# eagle_eagle_Tiltaudio_3_6.net
KiCad netlist of a schematic drawn in EAGLE
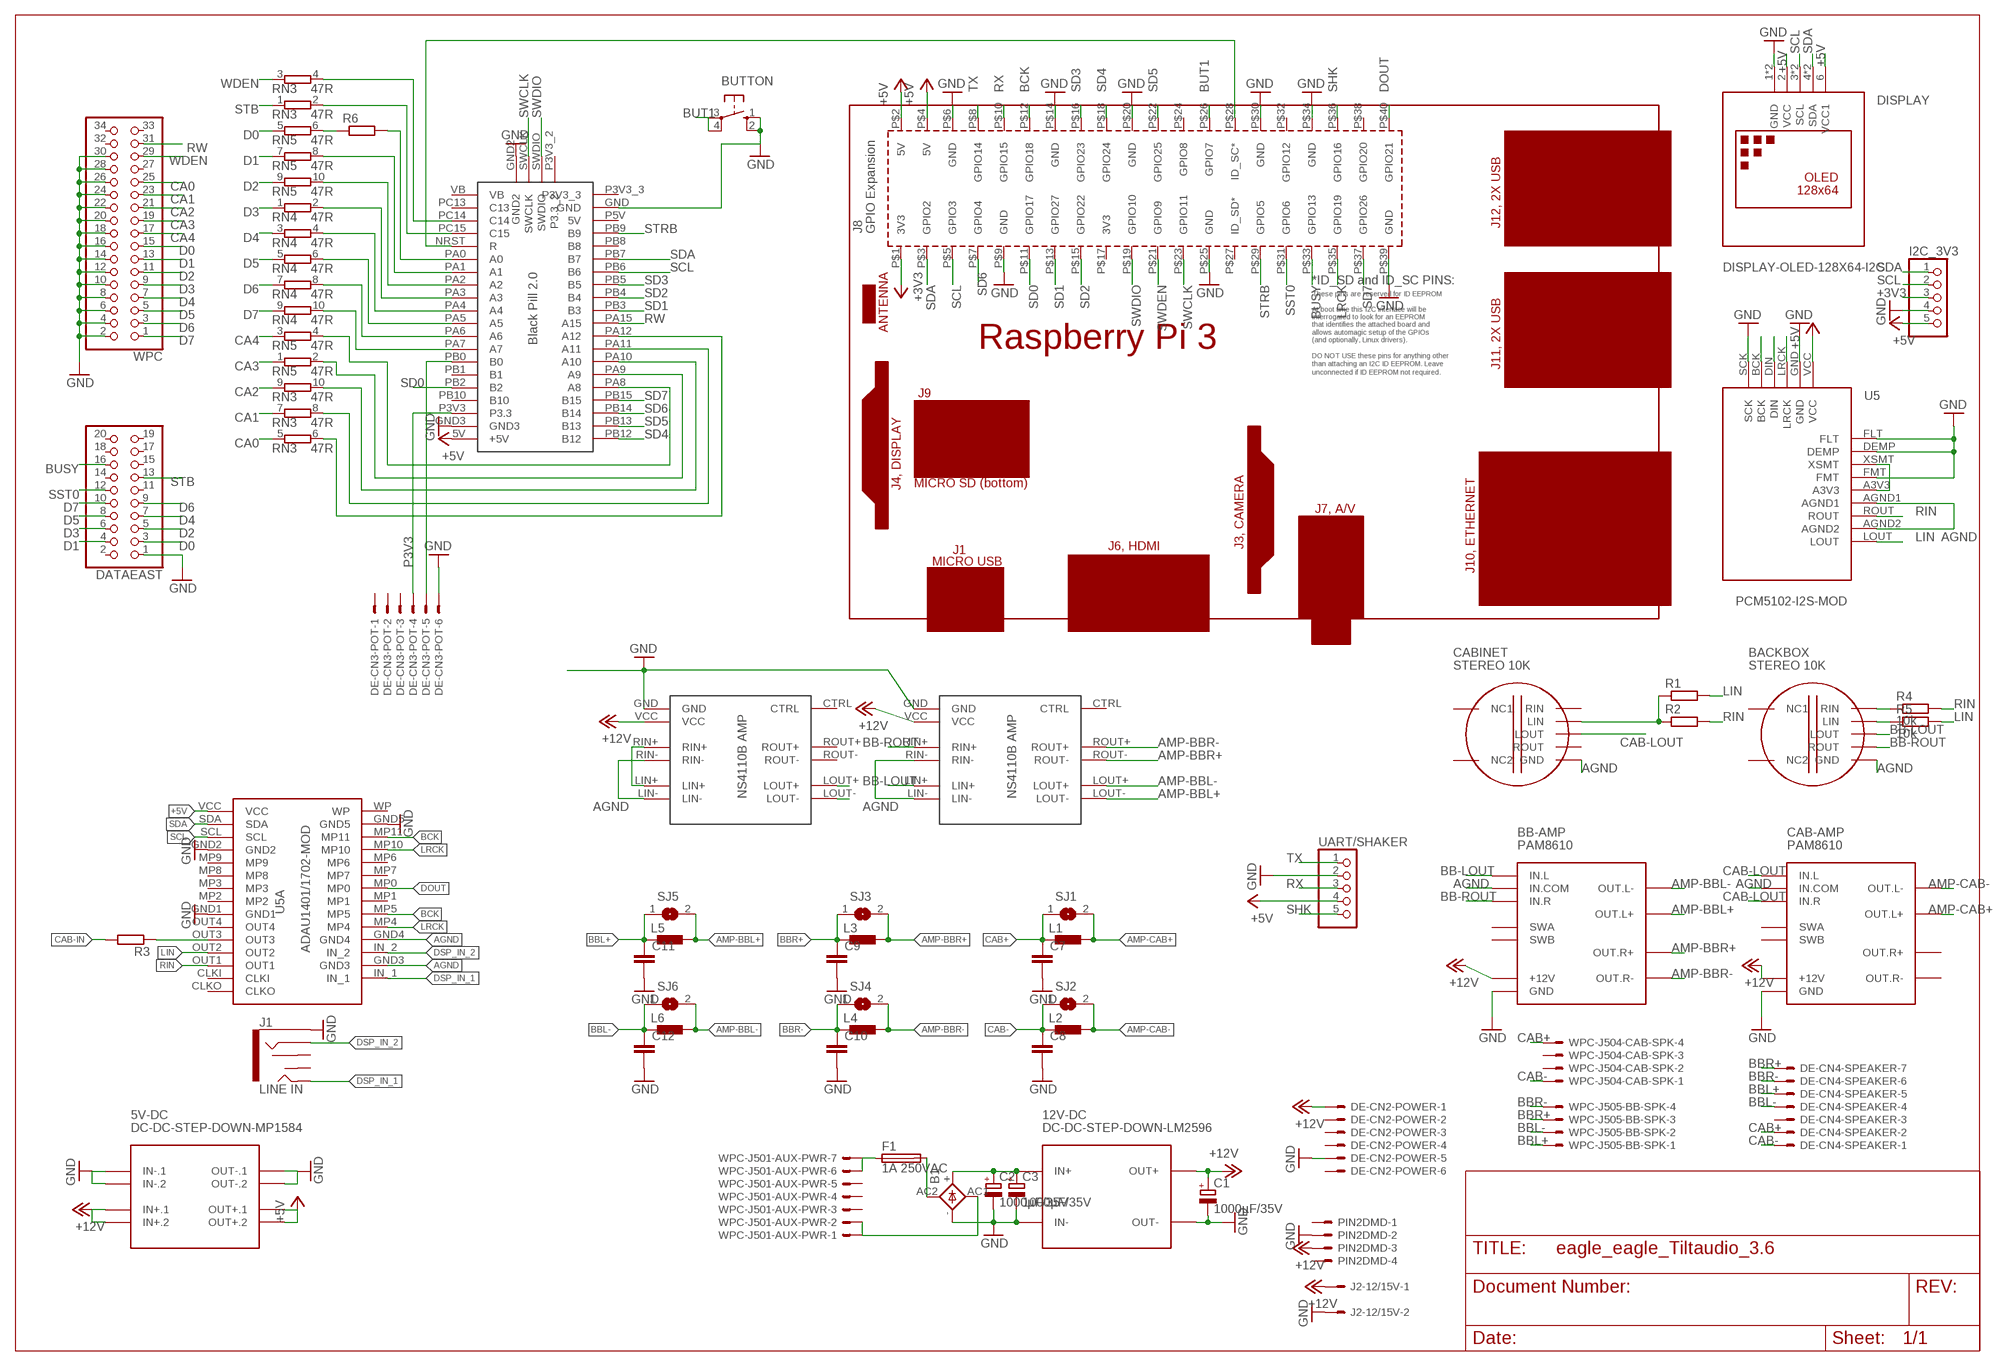
[diagram p0: schematic, sheet 1]

(export (version "E")
  (design (tool "Eeschema 10.0.6"))
  (components
    (comp (ref "5V-DC")
      (value "DC-DC-STEP-DOWN-MP1584")
      (footprint "eagle-import:DC-DC-STEP-DOWN-MP1584")
      (libsource (lib "eagle-import") (part "DC-DC-STEP-DOWN-MP1584"))
    )
    (comp (ref "12V-DC")
      (value "DC-DC-STEP-DOWN-LM2596")
      (footprint "eagle-import:DC-DC-STEP-DOWN-LM2596")
      (libsource (lib "eagle-import") (part "DC-DC-STEP-DOWN-LM2596"))
    )
    (comp (ref "B1")
      (value "KBL")
      (footprint "eagle-import:KBL")
      (libsource (lib "eagle-import") (part "KBL"))
    )
    (comp (ref "BACKBOX")
      (value "STEREO 10K")
      (footprint "eagle-import:UXCELL-STEREO-POTENTIOMETER")
      (libsource (lib "eagle-import") (part "UXCELL-STEREO-POTENTIOMETER"))
    )
    (comp (ref "BB-AMP")
      (value "PAM8610")
      (footprint "eagle-import:AMPLIFIER-PAM8610")
      (libsource (lib "eagle-import") (part "AMPLIFIER-PAM8610"))
    )
    (comp (ref "BUTTON")
      (value "10-XX")
      (footprint "eagle-import:B3F-10XX")
      (fields (field (name "MPN") "B3F-1000"))
      (libsource (lib "eagle-import") (part "10-XX"))
    )
    (comp (ref "C1")
      (value "1000µF/35V")
      (footprint "eagle-import:E5-13")
      (libsource (lib "eagle-import") (part "CPOL-EUE5-13"))
    )
    (comp (ref "C2")
      (value "1000µF/35V")
      (footprint "eagle-import:E5-13")
      (libsource (lib "eagle-import") (part "CPOL-EUE5-13"))
    )
    (comp (ref "C3")
      (value "1000µF/35V")
      (footprint "eagle-import:E5-13")
      (libsource (lib "eagle-import") (part "CPOL-EUE5-13"))
    )
    (comp (ref "C7")
      (value "C-EU050-025X075")
      (footprint "eagle-import:C050-025X075")
      (libsource (lib "eagle-import") (part "C-EU050-025X075"))
    )
    (comp (ref "C8")
      (value "C-EU050-025X075")
      (footprint "eagle-import:C050-025X075")
      (libsource (lib "eagle-import") (part "C-EU050-025X075"))
    )
    (comp (ref "C9")
      (value "C-EU050-025X075")
      (footprint "eagle-import:C050-025X075")
      (libsource (lib "eagle-import") (part "C-EU050-025X075"))
    )
    (comp (ref "C10")
      (value "C-EU050-025X075")
      (footprint "eagle-import:C050-025X075")
      (libsource (lib "eagle-import") (part "C-EU050-025X075"))
    )
    (comp (ref "C11")
      (value "C-EU050-025X075")
      (footprint "eagle-import:C050-025X075")
      (libsource (lib "eagle-import") (part "C-EU050-025X075"))
    )
    (comp (ref "C12")
      (value "C-EU050-025X075")
      (footprint "eagle-import:C050-025X075")
      (libsource (lib "eagle-import") (part "C-EU050-025X075"))
    )
    (comp (ref "CAB-AMP")
      (value "PAM8610")
      (footprint "eagle-import:AMPLIFIER-PAM8610")
      (libsource (lib "eagle-import") (part "AMPLIFIER-PAM8610"))
    )
    (comp (ref "CABINET")
      (value "STEREO 10K")
      (footprint "eagle-import:UXCELL-STEREO-POTENTIOMETER")
      (libsource (lib "eagle-import") (part "UXCELL-STEREO-POTENTIOMETER"))
    )
    (comp (ref "DATAEAST")
      (value "PINHD-2X10")
      (footprint "eagle-import:2X10")
      (libsource (lib "eagle-import") (part "PINHD-2X10"))
    )
    (comp (ref "DE-CN2-POWER")
      (value "KK-156-6")
      (footprint "eagle-import:KK-156-6")
      (libsource (lib "eagle-import") (part "KK-156-6"))
    )
    (comp (ref "DE-CN3-POT")
      (value "KK-156-6")
      (footprint "eagle-import:KK-156-6")
      (libsource (lib "eagle-import") (part "KK-156-6"))
    )
    (comp (ref "DE-CN4-SPEAKER")
      (value "KK-156-7")
      (footprint "eagle-import:KK-156-7")
      (libsource (lib "eagle-import") (part "KK-156-7"))
    )
    (comp (ref "DISPLAY")
      (value "DISPLAY-OLED-128X64-I2C")
      (footprint "eagle-import:DISPLAY-OLED-128X64-I2C")
      (libsource (lib "eagle-import") (part "DISPLAY-OLED-128X64-I2C"))
    )
    (comp (ref "F1")
      (value "1A 250VAC")
      (footprint "eagle-import:SHK20L")
      (libsource (lib "eagle-import") (part "FUSESHK20L"))
    )
    (comp (ref "I2C_3V3")
      (value "PINHD-1X5")
      (footprint "eagle-import:1X05")
      (libsource (lib "eagle-import") (part "PINHD-1X5"))
    )
    (comp (ref "J1")
      (value "LINE IN")
      (footprint "eagle-import:AUDIO-JACK")
      (libsource (lib "eagle-import") (part "AUDIO_JACK_3.5MM_PTH"))
    )
    (comp (ref "J2-12/15V")
      (value "KK-156-2")
      (footprint "eagle-import:KK-156-2")
      (libsource (lib "eagle-import") (part "KK-156-2"))
    )
    (comp (ref "L1")
      (value "BL02RN1")
      (footprint "eagle-import:BL02RN1")
      (libsource (lib "eagle-import") (part "BL02RN1"))
    )
    (comp (ref "L2")
      (value "BL02RN1")
      (footprint "eagle-import:BL02RN1")
      (libsource (lib "eagle-import") (part "BL02RN1"))
    )
    (comp (ref "L3")
      (value "BL02RN1")
      (footprint "eagle-import:BL02RN1")
      (libsource (lib "eagle-import") (part "BL02RN1"))
    )
    (comp (ref "L4")
      (value "BL02RN1")
      (footprint "eagle-import:BL02RN1")
      (libsource (lib "eagle-import") (part "BL02RN1"))
    )
    (comp (ref "L5")
      (value "BL02RN1")
      (footprint "eagle-import:BL02RN1")
      (libsource (lib "eagle-import") (part "BL02RN1"))
    )
    (comp (ref "L6")
      (value "BL02RN1")
      (footprint "eagle-import:BL02RN1")
      (libsource (lib "eagle-import") (part "BL02RN1"))
    )
    (comp (ref "MPU1")
      (value "Raspberry Pi3")
      (footprint "eagle-import:RPI3MIRROR")
      (libsource (lib "eagle-import") (part "RPI3RPI3MIRROR"))
    )
    (comp (ref "PIN2DMD")
      (value "KK-156-4")
      (footprint "eagle-import:KK-156-4")
      (libsource (lib "eagle-import") (part "KK-156-4"))
    )
    (comp (ref "R1")
      (value "R-EU_0207/10")
      (footprint "eagle-import:0207_10")
      (libsource (lib "eagle-import") (part "R-EU_0207/10"))
    )
    (comp (ref "R2")
      (value "R-EU_0207/10")
      (footprint "eagle-import:0207_10")
      (libsource (lib "eagle-import") (part "R-EU_0207/10"))
    )
    (comp (ref "R3")
      (value "R-EU_0207/10")
      (footprint "eagle-import:0207_10")
      (libsource (lib "eagle-import") (part "R-EU_0207/10"))
    )
    (comp (ref "R4")
      (value "10k")
      (footprint "eagle-import:0207_10")
      (libsource (lib "eagle-import") (part "R-EU_0207/10"))
    )
    (comp (ref "R5")
      (value "10k")
      (footprint "eagle-import:0207_10")
      (libsource (lib "eagle-import") (part "R-EU_0207/10"))
    )
    (comp (ref "R6")
      (value "R-EU_0207/12")
      (footprint "eagle-import:0207_12")
      (libsource (lib "eagle-import") (part "R-EU_0207/12"))
    )
    (comp (ref "RN3")
      (value "47R")
      (footprint "eagle-import:SIL10")
      (libsource (lib "eagle-import") (part "E5RP"))
    )
    (comp (ref "RN4")
      (value "47R")
      (footprint "eagle-import:SIL10")
      (libsource (lib "eagle-import") (part "E5RP"))
    )
    (comp (ref "RN5")
      (value "47R")
      (footprint "eagle-import:SIL10")
      (libsource (lib "eagle-import") (part "E5RP"))
    )
    (comp (ref "SJ1") (value "SJ") (footprint "eagle-import:SJ") (libsource (lib "eagle-import") (part "SJ")))
    (comp (ref "SJ2") (value "SJ") (footprint "eagle-import:SJ") (libsource (lib "eagle-import") (part "SJ")))
    (comp (ref "SJ3") (value "SJ") (footprint "eagle-import:SJ") (libsource (lib "eagle-import") (part "SJ")))
    (comp (ref "SJ4") (value "SJ") (footprint "eagle-import:SJ") (libsource (lib "eagle-import") (part "SJ")))
    (comp (ref "SJ5") (value "SJ") (footprint "eagle-import:SJ") (libsource (lib "eagle-import") (part "SJ")))
    (comp (ref "SJ6") (value "SJ") (footprint "eagle-import:SJ") (libsource (lib "eagle-import") (part "SJ")))
    (comp (ref "U$1")
      (value "STM32F411CE-BLACKPILL")
      (footprint "eagle-import:DIL40")
      (libsource (lib "eagle-import") (part "STM32F411CE-BLACKPILL"))
    )
    (comp (ref "U$2")
      (value "DAMP")
      (footprint "eagle-import:DAMP")
      (libsource (lib "eagle-import") (part "DAMP"))
    )
    (comp (ref "U$3")
      (value "DAMP")
      (footprint "eagle-import:DAMP")
      (libsource (lib "eagle-import") (part "DAMP"))
    )
    (comp (ref "U5")
      (value "PCM5102-I2S-MOD")
      (footprint "eagle-import:PCM5102-I2S-MOD")
      (libsource (lib "eagle-import") (part "PCM5102-I2S-MOD"))
    )
    (comp (ref "U5A")
      (value "ADAU1401/1702-MOD")
      (footprint "eagle-import:ADAU1401_1701-MOD")
      (libsource (lib "eagle-import") (part "ADAU1401/1702-MOD"))
    )
    (comp (ref "UART/SHAKER")
      (value "PINHD-1X5")
      (footprint "eagle-import:1X05")
      (libsource (lib "eagle-import") (part "PINHD-1X5"))
    )
    (comp (ref "WPC")
      (value "PINHD-2X17")
      (footprint "eagle-import:2X17")
      (libsource (lib "eagle-import") (part "PINHD-2X17"))
    )
    (comp (ref "WPC-J501-AUX-PWR")
      (value "KK-156-7")
      (footprint "eagle-import:KK-156-7")
      (libsource (lib "eagle-import") (part "KK-156-7"))
    )
    (comp (ref "WPC-J504-CAB-SPK")
      (value "KK-156-4")
      (footprint "eagle-import:KK-156-4")
      (libsource (lib "eagle-import") (part "KK-156-4"))
    )
    (comp (ref "WPC-J505-BB-SPK")
      (value "KK-156-4")
      (footprint "eagle-import:KK-156-4")
      (libsource (lib "eagle-import") (part "KK-156-4"))
    )
  )
  (nets
    (net (code "1") (name "+3V3") (class "Default")
      (node (ref "I2C_3V3") (pin "3") (pinfunction "3_3") (pintype "passive"))
      (node (ref "MPU1") (pin "P$1") (pinfunction "3V3_P$1") (pintype "bidirectional"))
    )
    (net (code "2") (name "+5V") (class "Default")
      (node (ref "5V-DC") (pin "OUT+.1") (pinfunction "OUT+.1_OUT+.1") (pintype "bidirectional"))
      (node (ref "5V-DC") (pin "OUT+.2") (pinfunction "OUT+.2_OUT+.2") (pintype "bidirectional"))
      (node (ref "DISPLAY") (pin "2") (pinfunction "VCC_2") (pintype "power_in"))
      (node (ref "DISPLAY") (pin "6") (pinfunction "VCC1_6") (pintype "power_in"))
      (node (ref "I2C_3V3") (pin "5") (pinfunction "5_5") (pintype "passive"))
      (node (ref "MPU1") (pin "P$2") (pinfunction "5V_P$2") (pintype "bidirectional"))
      (node (ref "MPU1") (pin "P$4") (pinfunction "5V_P$4") (pintype "bidirectional"))
      (node (ref "U$1") (pin "5V") (pinfunction "+5V_5V") (pintype "bidirectional"))
      (node (ref "U5") (pin "VCC") (pinfunction "VCC_VCC") (pintype "bidirectional"))
      (node (ref "U5A") (pin "VCC") (pinfunction "VCC_VCC") (pintype "bidirectional"))
      (node (ref "UART/SHAKER") (pin "4") (pinfunction "4_4") (pintype "passive"))
    )
    (net (code "3") (name "+12V") (class "Default")
      (node (ref "12V-DC") (pin "OUT+") (pinfunction "OUT+_OUT+") (pintype "bidirectional"))
      (node (ref "5V-DC") (pin "IN+.1") (pinfunction "IN+.1_IN+.1") (pintype "bidirectional"))
      (node (ref "5V-DC") (pin "IN+.2") (pinfunction "IN+.2_IN+.2") (pintype "bidirectional"))
      (node (ref "BB-AMP") (pin "+12V") (pinfunction "+12V_+12V") (pintype "power_in"))
      (node (ref "C1") (pin "+") (pinfunction "+_+") (pintype "passive"))
      (node (ref "CAB-AMP") (pin "+12V") (pinfunction "+12V_+12V") (pintype "power_in"))
      (node (ref "DE-CN2-POWER") (pin "1") (pinfunction "S_1") (pintype "passive"))
      (node (ref "J2-12/15V") (pin "1") (pinfunction "S_1") (pintype "passive"))
      (node (ref "PIN2DMD") (pin "3") (pinfunction "S_3") (pintype "passive"))
      (node (ref "U$2") (pin "VCC") (pinfunction "VCC_VCC") (pintype "bidirectional"))
      (node (ref "U$3") (pin "VCC") (pinfunction "VCC_VCC") (pintype "bidirectional"))
    )
    (net (code "4") (name "/BB-LOUT") (class "Default")
      (node (ref "BACKBOX") (pin "LOUT") (pinfunction "LOUT_LOUT") (pintype "bidirectional"))
      (node (ref "BB-AMP") (pin "IN.L") (pinfunction "IN.L_IN.L") (pintype "input"))
      (node (ref "U$2") (pin "LIN+") (pinfunction "LIN+_LIN+") (pintype "bidirectional"))
    )
    (net (code "5") (name "/BB-ROUT") (class "Default")
      (node (ref "BACKBOX") (pin "ROUT") (pinfunction "ROUT_ROUT") (pintype "bidirectional"))
      (node (ref "BB-AMP") (pin "IN.R") (pinfunction "IN.R_IN.R") (pintype "bidirectional"))
      (node (ref "U$2") (pin "RIN+") (pinfunction "RIN+_RIN+") (pintype "bidirectional"))
    )
    (net (code "6") (name "/BUSY") (class "Default")
      (node (ref "DATAEAST") (pin "16") (pinfunction "16_16") (pintype "passive"))
      (node (ref "MPU1") (pin "P$33") (pinfunction "GPIO13_P$33") (pintype "bidirectional"))
    )
    (net (code "7") (name "/BUT1") (class "Default")
      (node (ref "BUTTON") (pin "3") (pinfunction "P_3") (pintype "passive"))
      (node (ref "BUTTON") (pin "4") (pinfunction "P1_4") (pintype "passive"))
      (node (ref "MPU1") (pin "P$26") (pinfunction "GPIO7_P$26") (pintype "bidirectional"))
    )
    (net (code "8") (name "/CA0") (class "Default")
      (node (ref "RN3") (pin "5") (pinfunction "1_5") (pintype "passive"))
      (node (ref "WPC") (pin "25") (pinfunction "25_25") (pintype "passive"))
    )
    (net (code "9") (name "/CA1") (class "Default")
      (node (ref "RN3") (pin "7") (pinfunction "1_7") (pintype "passive"))
      (node (ref "WPC") (pin "23") (pinfunction "23_23") (pintype "passive"))
    )
    (net (code "10") (name "/CA2") (class "Default")
      (node (ref "RN3") (pin "9") (pinfunction "1_9") (pintype "passive"))
      (node (ref "WPC") (pin "21") (pinfunction "21_21") (pintype "passive"))
    )
    (net (code "11") (name "/CA3") (class "Default")
      (node (ref "RN5") (pin "1") (pinfunction "1_1") (pintype "passive"))
      (node (ref "WPC") (pin "19") (pinfunction "19_19") (pintype "passive"))
    )
    (net (code "12") (name "/CA4") (class "Default")
      (node (ref "RN5") (pin "3") (pinfunction "1_3") (pintype "passive"))
      (node (ref "WPC") (pin "17") (pinfunction "17_17") (pintype "passive"))
    )
    (net (code "13") (name "/CAB-LOUT") (class "Default")
      (node (ref "CAB-AMP") (pin "IN.L") (pinfunction "IN.L_IN.L") (pintype "input"))
      (node (ref "CAB-AMP") (pin "IN.R") (pinfunction "IN.R_IN.R") (pintype "bidirectional"))
      (node (ref "CABINET") (pin "LOUT") (pinfunction "LOUT_LOUT") (pintype "bidirectional"))
      (node (ref "U$3") (pin "LIN+") (pinfunction "LIN+_LIN+") (pintype "bidirectional"))
      (node (ref "U$3") (pin "RIN+") (pinfunction "RIN+_RIN+") (pintype "bidirectional"))
    )
    (net (code "14") (name "/D0") (class "Default")
      (node (ref "DATAEAST") (pin "3") (pinfunction "3_3") (pintype "passive"))
      (node (ref "RN5") (pin "5") (pinfunction "1_5") (pintype "passive"))
      (node (ref "WPC") (pin "15") (pinfunction "15_15") (pintype "passive"))
    )
    (net (code "15") (name "/D1") (class "Default")
      (node (ref "DATAEAST") (pin "4") (pinfunction "4_4") (pintype "passive"))
      (node (ref "RN5") (pin "7") (pinfunction "1_7") (pintype "passive"))
      (node (ref "WPC") (pin "13") (pinfunction "13_13") (pintype "passive"))
    )
    (net (code "16") (name "/D2") (class "Default")
      (node (ref "DATAEAST") (pin "5") (pinfunction "5_5") (pintype "passive"))
      (node (ref "RN5") (pin "9") (pinfunction "1_9") (pintype "passive"))
      (node (ref "WPC") (pin "11") (pinfunction "11_11") (pintype "passive"))
    )
    (net (code "17") (name "/D3") (class "Default")
      (node (ref "DATAEAST") (pin "6") (pinfunction "6_6") (pintype "passive"))
      (node (ref "RN4") (pin "1") (pinfunction "1_1") (pintype "passive"))
      (node (ref "WPC") (pin "9") (pinfunction "9_9") (pintype "passive"))
    )
    (net (code "18") (name "/D4") (class "Default")
      (node (ref "DATAEAST") (pin "7") (pinfunction "7_7") (pintype "passive"))
      (node (ref "RN4") (pin "3") (pinfunction "1_3") (pintype "passive"))
      (node (ref "WPC") (pin "7") (pinfunction "7_7") (pintype "passive"))
    )
    (net (code "19") (name "/D5") (class "Default")
      (node (ref "DATAEAST") (pin "8") (pinfunction "8_8") (pintype "passive"))
      (node (ref "RN4") (pin "5") (pinfunction "1_5") (pintype "passive"))
      (node (ref "WPC") (pin "5") (pinfunction "5_5") (pintype "passive"))
    )
    (net (code "20") (name "/D6") (class "Default")
      (node (ref "DATAEAST") (pin "9") (pinfunction "9_9") (pintype "passive"))
      (node (ref "RN4") (pin "7") (pinfunction "1_7") (pintype "passive"))
      (node (ref "WPC") (pin "3") (pinfunction "3_3") (pintype "passive"))
    )
    (net (code "21") (name "/D7") (class "Default")
      (node (ref "DATAEAST") (pin "10") (pinfunction "10_10") (pintype "passive"))
      (node (ref "RN4") (pin "9") (pinfunction "1_9") (pintype "passive"))
      (node (ref "WPC") (pin "1") (pinfunction "1_1") (pintype "passive"))
    )
    (net (code "22") (name "/P3V3") (class "Default")
      (node (ref "DE-CN3-POT") (pin "4") (pinfunction "S_4") (pintype "passive"))
      (node (ref "U$1") (pin "P3V3") (pinfunction "P3.3_P3V3") (pintype "bidirectional"))
    )
    (net (code "23") (name "/RW") (class "Default")
      (node (ref "U$1") (pin "PA15") (pinfunction "A15_PA15") (pintype "bidirectional"))
      (node (ref "WPC") (pin "31") (pinfunction "31_31") (pintype "passive"))
    )
    (net (code "24") (name "/RX") (class "Default")
      (node (ref "MPU1") (pin "P$10") (pinfunction "GPIO15_P$10") (pintype "bidirectional"))
      (node (ref "UART/SHAKER") (pin "3") (pinfunction "3_3") (pintype "passive"))
    )
    (net (code "25") (name "/SD0") (class "Default")
      (node (ref "MPU1") (pin "P$11") (pinfunction "GPIO17_P$11") (pintype "bidirectional"))
      (node (ref "U$1") (pin "PB2") (pinfunction "B2_PB2") (pintype "bidirectional"))
    )
    (net (code "26") (name "/SD1") (class "Default")
      (node (ref "MPU1") (pin "P$13") (pinfunction "GPIO27_P$13") (pintype "bidirectional"))
      (node (ref "U$1") (pin "PB3") (pinfunction "B3_PB3") (pintype "bidirectional"))
    )
    (net (code "27") (name "/SD2") (class "Default")
      (node (ref "MPU1") (pin "P$15") (pinfunction "GPIO22_P$15") (pintype "bidirectional"))
      (node (ref "U$1") (pin "PB4") (pinfunction "B4_PB4") (pintype "bidirectional"))
    )
    (net (code "28") (name "/SD3") (class "Default")
      (node (ref "MPU1") (pin "P$16") (pinfunction "GPIO23_P$16") (pintype "bidirectional"))
      (node (ref "U$1") (pin "PB5") (pinfunction "B5_PB5") (pintype "bidirectional"))
    )
    (net (code "29") (name "/SD4") (class "Default")
      (node (ref "MPU1") (pin "P$18") (pinfunction "GPIO24_P$18") (pintype "bidirectional"))
      (node (ref "U$1") (pin "PB12") (pinfunction "B12_PB12") (pintype "bidirectional"))
    )
    (net (code "30") (name "/SD5") (class "Default")
      (node (ref "MPU1") (pin "P$22") (pinfunction "GPIO25_P$22") (pintype "bidirectional"))
      (node (ref "U$1") (pin "PB13") (pinfunction "B13_PB13") (pintype "bidirectional"))
    )
    (net (code "31") (name "/SD6") (class "Default")
      (node (ref "MPU1") (pin "P$7") (pinfunction "GPIO4_P$7") (pintype "bidirectional"))
      (node (ref "U$1") (pin "PB14") (pinfunction "B14_PB14") (pintype "bidirectional"))
    )
    (net (code "32") (name "/SD7") (class "Default")
      (node (ref "MPU1") (pin "P$37") (pinfunction "GPIO26_P$37") (pintype "bidirectional"))
      (node (ref "U$1") (pin "PB15") (pinfunction "B15_PB15") (pintype "bidirectional"))
    )
    (net (code "33") (name "/SHK") (class "Default")
      (node (ref "MPU1") (pin "P$36") (pinfunction "GPIO16_P$36") (pintype "bidirectional"))
      (node (ref "UART/SHAKER") (pin "5") (pinfunction "5_5") (pintype "passive"))
    )
    (net (code "34") (name "/SST0") (class "Default")
      (node (ref "DATAEAST") (pin "12") (pinfunction "12_12") (pintype "passive"))
      (node (ref "MPU1") (pin "P$31") (pinfunction "GPIO6_P$31") (pintype "bidirectional"))
    )
    (net (code "35") (name "/STB") (class "Default")
      (node (ref "DATAEAST") (pin "13") (pinfunction "13_13") (pintype "passive"))
      (node (ref "RN3") (pin "1") (pinfunction "1_1") (pintype "passive"))
    )
    (net (code "36") (name "/STRB") (class "Default")
      (node (ref "MPU1") (pin "P$29") (pinfunction "GPIO5_P$29") (pintype "bidirectional"))
      (node (ref "U$1") (pin "PB9") (pinfunction "B9_PB9") (pintype "bidirectional"))
    )
    (net (code "37") (name "/SWCLK") (class "Default")
      (node (ref "MPU1") (pin "P$23") (pinfunction "GPIO11_P$23") (pintype "bidirectional"))
      (node (ref "U$1") (pin "SWCLK") (pinfunction "SWCLK_SWCLK") (pintype "bidirectional"))
    )
    (net (code "38") (name "/SWDEN") (class "Default")
      (node (ref "MPU1") (pin "P$21") (pinfunction "GPIO9_P$21") (pintype "bidirectional"))
    )
    (net (code "39") (name "/SWDIO") (class "Default")
      (node (ref "MPU1") (pin "P$19") (pinfunction "GPIO10_P$19") (pintype "bidirectional"))
      (node (ref "U$1") (pin "SWDIO") (pinfunction "SWDIO_SWDIO") (pintype "bidirectional"))
    )
    (net (code "40") (name "/TX") (class "Default")
      (node (ref "MPU1") (pin "P$8") (pinfunction "GPIO14_P$8") (pintype "bidirectional"))
      (node (ref "UART/SHAKER") (pin "1") (pinfunction "1_1") (pintype "passive"))
    )
    (net (code "41") (name "/WDEN") (class "Default")
      (node (ref "RN3") (pin "3") (pinfunction "1_3") (pintype "passive"))
      (node (ref "WPC") (pin "29") (pinfunction "29_29") (pintype "passive"))
    )
    (net (code "42") (name "AGND") (class "Default")
      (node (ref "BACKBOX") (pin "GND") (pinfunction "GND_GND") (pintype "bidirectional"))
      (node (ref "BB-AMP") (pin "IN.COM") (pinfunction "IN.COM_IN.COM") (pintype "input"))
      (node (ref "CAB-AMP") (pin "IN.COM") (pinfunction "IN.COM_IN.COM") (pintype "input"))
      (node (ref "CABINET") (pin "GND") (pinfunction "GND_GND") (pintype "bidirectional"))
      (node (ref "U$2") (pin "LIN-") (pinfunction "LIN-_LIN-") (pintype "bidirectional"))
      (node (ref "U$2") (pin "RIN-") (pinfunction "RIN-_RIN-") (pintype "bidirectional"))
      (node (ref "U$3") (pin "LIN-") (pinfunction "LIN-_LIN-") (pintype "bidirectional"))
      (node (ref "U$3") (pin "RIN-") (pinfunction "RIN-_RIN-") (pintype "bidirectional"))
      (node (ref "U5") (pin "AGND1") (pinfunction "AGND1_AGND1") (pintype "bidirectional"))
      (node (ref "U5") (pin "AGND2") (pinfunction "AGND2_AGND2") (pintype "bidirectional"))
      (node (ref "U5A") (pin "GND3") (pinfunction "GND3_GND3") (pintype "bidirectional"))
      (node (ref "U5A") (pin "GND4") (pinfunction "GND4_GND4") (pintype "bidirectional"))
    )
    (net (code "43") (name "AMP-BBL+") (class "Default")
      (node (ref "BB-AMP") (pin "OUT.L+") (pinfunction "OUT.L+_OUT.L+") (pintype "output"))
      (node (ref "L5") (pin "2") (pinfunction "2_2") (pintype "passive"))
      (node (ref "SJ5") (pin "2") (pinfunction "2_2") (pintype "passive"))
      (node (ref "U$2") (pin "LOUT-") (pinfunction "LOUT-_LOUT-") (pintype "bidirectional"))
    )
    (net (code "44") (name "AMP-BBL-") (class "Default")
      (node (ref "BB-AMP") (pin "OUT.L-") (pinfunction "OUT.L-_OUT.L-") (pintype "output"))
      (node (ref "L6") (pin "2") (pinfunction "2_2") (pintype "passive"))
      (node (ref "SJ6") (pin "2") (pinfunction "2_2") (pintype "passive"))
      (node (ref "U$2") (pin "LOUT+") (pinfunction "LOUT+_LOUT+") (pintype "bidirectional"))
    )
    (net (code "45") (name "AMP-BBR+") (class "Default")
      (node (ref "BB-AMP") (pin "OUT.R+") (pinfunction "OUT.R+_OUT.R+") (pintype "output"))
      (node (ref "L3") (pin "2") (pinfunction "2_2") (pintype "passive"))
      (node (ref "SJ3") (pin "2") (pinfunction "2_2") (pintype "passive"))
      (node (ref "U$2") (pin "ROUT-") (pinfunction "ROUT-_ROUT-") (pintype "bidirectional"))
    )
    (net (code "46") (name "AMP-BBR-") (class "Default")
      (node (ref "BB-AMP") (pin "OUT.R-") (pinfunction "OUT.R-_OUT.R-") (pintype "output"))
      (node (ref "L4") (pin "2") (pinfunction "2_2") (pintype "passive"))
      (node (ref "SJ4") (pin "2") (pinfunction "2_2") (pintype "passive"))
      (node (ref "U$2") (pin "ROUT+") (pinfunction "ROUT+_ROUT+") (pintype "bidirectional"))
    )
    (net (code "47") (name "AMP-CAB+") (class "Default")
      (node (ref "CAB-AMP") (pin "OUT.L+") (pinfunction "OUT.L+_OUT.L+") (pintype "output"))
      (node (ref "L1") (pin "2") (pinfunction "2_2") (pintype "passive"))
      (node (ref "SJ1") (pin "2") (pinfunction "2_2") (pintype "passive"))
      (node (ref "U$3") (pin "LOUT-") (pinfunction "LOUT-_LOUT-") (pintype "bidirectional"))
    )
    (net (code "48") (name "AMP-CAB-") (class "Default")
      (node (ref "CAB-AMP") (pin "OUT.L-") (pinfunction "OUT.L-_OUT.L-") (pintype "output"))
      (node (ref "L2") (pin "2") (pinfunction "2_2") (pintype "passive"))
      (node (ref "SJ2") (pin "2") (pinfunction "2_2") (pintype "passive"))
      (node (ref "U$3") (pin "LOUT+") (pinfunction "LOUT+_LOUT+") (pintype "bidirectional"))
    )
    (net (code "49") (name "BBL+") (class "Default")
      (node (ref "C11") (pin "1") (pinfunction "1_1") (pintype "passive"))
      (node (ref "DE-CN4-SPEAKER") (pin "5") (pinfunction "S_5") (pintype "passive"))
      (node (ref "L5") (pin "1") (pinfunction "1_1") (pintype "passive"))
      (node (ref "SJ5") (pin "1") (pinfunction "1_1") (pintype "passive"))
      (node (ref "WPC-J505-BB-SPK") (pin "1") (pinfunction "S_1") (pintype "passive"))
    )
    (net (code "50") (name "BBL-") (class "Default")
      (node (ref "C12") (pin "1") (pinfunction "1_1") (pintype "passive"))
      (node (ref "DE-CN4-SPEAKER") (pin "4") (pinfunction "S_4") (pintype "passive"))
      (node (ref "L6") (pin "1") (pinfunction "1_1") (pintype "passive"))
      (node (ref "SJ6") (pin "1") (pinfunction "1_1") (pintype "passive"))
      (node (ref "WPC-J505-BB-SPK") (pin "2") (pinfunction "S_2") (pintype "passive"))
    )
    (net (code "51") (name "BBR+") (class "Default")
      (node (ref "C9") (pin "1") (pinfunction "1_1") (pintype "passive"))
      (node (ref "DE-CN4-SPEAKER") (pin "7") (pinfunction "S_7") (pintype "passive"))
      (node (ref "L3") (pin "1") (pinfunction "1_1") (pintype "passive"))
      (node (ref "SJ3") (pin "1") (pinfunction "1_1") (pintype "passive"))
      (node (ref "WPC-J505-BB-SPK") (pin "3") (pinfunction "S_3") (pintype "passive"))
    )
    (net (code "52") (name "BBR-") (class "Default")
      (node (ref "C10") (pin "1") (pinfunction "1_1") (pintype "passive"))
      (node (ref "DE-CN4-SPEAKER") (pin "6") (pinfunction "S_6") (pintype "passive"))
      (node (ref "L4") (pin "1") (pinfunction "1_1") (pintype "passive"))
      (node (ref "SJ4") (pin "1") (pinfunction "1_1") (pintype "passive"))
      (node (ref "WPC-J505-BB-SPK") (pin "4") (pinfunction "S_4") (pintype "passive"))
    )
    (net (code "53") (name "BCK") (class "Default")
      (node (ref "MPU1") (pin "P$12") (pinfunction "GPIO18_P$12") (pintype "bidirectional"))
      (node (ref "U5") (pin "BCK") (pinfunction "BCK_BCK") (pintype "bidirectional"))
      (node (ref "U5A") (pin "MP11") (pinfunction "MP11_MP11") (pintype "bidirectional"))
      (node (ref "U5A") (pin "MP5") (pinfunction "MP5_MP5") (pintype "bidirectional"))
    )
    (net (code "54") (name "CAB+") (class "Default")
      (node (ref "C7") (pin "1") (pinfunction "1_1") (pintype "passive"))
      (node (ref "DE-CN4-SPEAKER") (pin "2") (pinfunction "S_2") (pintype "passive"))
      (node (ref "L1") (pin "1") (pinfunction "1_1") (pintype "passive"))
      (node (ref "SJ1") (pin "1") (pinfunction "1_1") (pintype "passive"))
      (node (ref "WPC-J504-CAB-SPK") (pin "4") (pinfunction "S_4") (pintype "passive"))
    )
    (net (code "55") (name "CAB-") (class "Default")
      (node (ref "C8") (pin "1") (pinfunction "1_1") (pintype "passive"))
      (node (ref "DE-CN4-SPEAKER") (pin "1") (pinfunction "S_1") (pintype "passive"))
      (node (ref "L2") (pin "1") (pinfunction "1_1") (pintype "passive"))
      (node (ref "SJ2") (pin "1") (pinfunction "1_1") (pintype "passive"))
      (node (ref "WPC-J504-CAB-SPK") (pin "1") (pinfunction "S_1") (pintype "passive"))
    )
    (net (code "56") (name "CAB-IN") (class "Default")
      (node (ref "CABINET") (pin "LIN") (pinfunction "LIN_LIN") (pintype "bidirectional"))
      (node (ref "R1") (pin "1") (pinfunction "1_1") (pintype "passive"))
      (node (ref "R2") (pin "1") (pinfunction "1_1") (pintype "passive"))
      (node (ref "R3") (pin "2") (pinfunction "2_2") (pintype "passive"))
    )
    (net (code "57") (name "DOUT") (class "Default")
      (node (ref "MPU1") (pin "P$40") (pinfunction "GPIO21_P$40") (pintype "bidirectional"))
      (node (ref "U5") (pin "DIN") (pinfunction "DIN_DIN") (pintype "bidirectional"))
      (node (ref "U5A") (pin "MP0") (pinfunction "MP0_MP0") (pintype "bidirectional"))
    )
    (net (code "58") (name "DSP_IN_1") (class "Default")
      (node (ref "J1") (pin "TIP") (pinfunction "TIP_TIP") (pintype "bidirectional"))
      (node (ref "U5A") (pin "IN_1") (pinfunction "IN_1_IN_1") (pintype "bidirectional"))
    )
    (net (code "59") (name "DSP_IN_2") (class "Default")
      (node (ref "J1") (pin "RING") (pinfunction "RING_RING") (pintype "bidirectional"))
      (node (ref "U5A") (pin "IN_2") (pinfunction "IN_2_IN_2") (pintype "bidirectional"))
    )
    (net (code "60") (name "GND") (class "Default")
      (node (ref "12V-DC") (pin "IN-") (pinfunction "IN-_IN-") (pintype "bidirectional"))
      (node (ref "12V-DC") (pin "OUT-") (pinfunction "OUT-_OUT-") (pintype "bidirectional"))
      (node (ref "5V-DC") (pin "IN-.1") (pinfunction "IN-.1_IN-.1") (pintype "bidirectional"))
      (node (ref "5V-DC") (pin "IN-.2") (pinfunction "IN-.2_IN-.2") (pintype "bidirectional"))
      (node (ref "5V-DC") (pin "OUT-.1") (pinfunction "OUT-.1_OUT-.1") (pintype "bidirectional"))
      (node (ref "5V-DC") (pin "OUT-.2") (pinfunction "OUT-.2_OUT-.2") (pintype "bidirectional"))
      (node (ref "B1") (pin "-") (pinfunction "-_-") (pintype "passive"))
      (node (ref "BB-AMP") (pin "GND") (pinfunction "GND_GND") (pintype "power_in"))
      (node (ref "BUTTON") (pin "1") (pinfunction "S_1") (pintype "passive"))
      (node (ref "BUTTON") (pin "2") (pinfunction "S1_2") (pintype "passive"))
      (node (ref "C1") (pin "-") (pinfunction "-_-") (pintype "passive"))
      (node (ref "C10") (pin "2") (pinfunction "2_2") (pintype "passive"))
      (node (ref "C11") (pin "2") (pinfunction "2_2") (pintype "passive"))
      (node (ref "C12") (pin "2") (pinfunction "2_2") (pintype "passive"))
      (node (ref "C2") (pin "-") (pinfunction "-_-") (pintype "passive"))
      (node (ref "C3") (pin "-") (pinfunction "-_-") (pintype "passive"))
      (node (ref "C7") (pin "2") (pinfunction "2_2") (pintype "passive"))
      (node (ref "C8") (pin "2") (pinfunction "2_2") (pintype "passive"))
      (node (ref "C9") (pin "2") (pinfunction "2_2") (pintype "passive"))
      (node (ref "CAB-AMP") (pin "GND") (pinfunction "GND_GND") (pintype "power_in"))
      (node (ref "DATAEAST") (pin "1") (pinfunction "1_1") (pintype "passive"))
      (node (ref "DE-CN2-POWER") (pin "5") (pinfunction "S_5") (pintype "passive"))
      (node (ref "DE-CN3-POT") (pin "6") (pinfunction "S_6") (pintype "passive"))
      (node (ref "DISPLAY") (pin "1") (pinfunction "GND_1") (pintype "power_in"))
      (node (ref "DISPLAY") (pin "5") (pinfunction "GND_5") (pintype "power_in"))
      (node (ref "I2C_3V3") (pin "4") (pinfunction "4_4") (pintype "passive"))
      (node (ref "J1") (pin "SLEEVE") (pinfunction "SLEEVE_SLEEVE") (pintype "bidirectional"))
      (node (ref "J2-12/15V") (pin "2") (pinfunction "S_2") (pintype "passive"))
      (node (ref "MPU1") (pin "P$14") (pinfunction "GND_P$14") (pintype "bidirectional"))
      (node (ref "MPU1") (pin "P$20") (pinfunction "GND_P$20") (pintype "bidirectional"))
      (node (ref "MPU1") (pin "P$25") (pinfunction "GND_P$25") (pintype "bidirectional"))
      (node (ref "MPU1") (pin "P$30") (pinfunction "GND_P$30") (pintype "bidirectional"))
      (node (ref "MPU1") (pin "P$34") (pinfunction "GND_P$34") (pintype "bidirectional"))
      (node (ref "MPU1") (pin "P$39") (pinfunction "GND_P$39") (pintype "bidirectional"))
      (node (ref "MPU1") (pin "P$6") (pinfunction "GND_P$6") (pintype "bidirectional"))
      (node (ref "MPU1") (pin "P$9") (pinfunction "GND_P$9") (pintype "bidirectional"))
      (node (ref "PIN2DMD") (pin "2") (pinfunction "S_2") (pintype "passive"))
      (node (ref "U$1") (pin "GND") (pinfunction "GND_GND") (pintype "bidirectional"))
      (node (ref "U$1") (pin "GND2") (pinfunction "GND2_GND2") (pintype "bidirectional"))
      (node (ref "U$1") (pin "GND3") (pinfunction "GND3_GND3") (pintype "bidirectional"))
      (node (ref "U$2") (pin "GND") (pinfunction "GND_GND") (pintype "bidirectional"))
      (node (ref "U$3") (pin "GND") (pinfunction "GND_GND") (pintype "bidirectional"))
      (node (ref "U5") (pin "DEMP") (pinfunction "DEMP_DEMP") (pintype "bidirectional"))
      (node (ref "U5") (pin "FLT") (pinfunction "FLT_FLT") (pintype "bidirectional"))
      (node (ref "U5") (pin "FMT") (pinfunction "FMT_FMT") (pintype "bidirectional"))
      (node (ref "U5") (pin "GND") (pinfunction "GND_GND") (pintype "bidirectional"))
      (node (ref "U5") (pin "SCK") (pinfunction "SCK_SCK") (pintype "bidirectional"))
      (node (ref "U5A") (pin "GND1") (pinfunction "GND1_GND1") (pintype "bidirectional"))
      (node (ref "U5A") (pin "GND2") (pinfunction "GND2_GND2") (pintype "bidirectional"))
      (node (ref "U5A") (pin "GND5") (pinfunction "GND5_GND5") (pintype "bidirectional"))
      (node (ref "UART/SHAKER") (pin "2") (pinfunction "2_2") (pintype "passive"))
      (node (ref "WPC") (pin "10") (pinfunction "10_10") (pintype "passive"))
      (node (ref "WPC") (pin "12") (pinfunction "12_12") (pintype "passive"))
      (node (ref "WPC") (pin "14") (pinfunction "14_14") (pintype "passive"))
      (node (ref "WPC") (pin "16") (pinfunction "16_16") (pintype "passive"))
      (node (ref "WPC") (pin "18") (pinfunction "18_18") (pintype "passive"))
      (node (ref "WPC") (pin "2") (pinfunction "2_2") (pintype "passive"))
      (node (ref "WPC") (pin "20") (pinfunction "20_20") (pintype "passive"))
      (node (ref "WPC") (pin "22") (pinfunction "22_22") (pintype "passive"))
      (node (ref "WPC") (pin "24") (pinfunction "24_24") (pintype "passive"))
      (node (ref "WPC") (pin "26") (pinfunction "26_26") (pintype "passive"))
      (node (ref "WPC") (pin "28") (pinfunction "28_28") (pintype "passive"))
      (node (ref "WPC") (pin "30") (pinfunction "30_30") (pintype "passive"))
      (node (ref "WPC") (pin "4") (pinfunction "4_4") (pintype "passive"))
      (node (ref "WPC") (pin "6") (pinfunction "6_6") (pintype "passive"))
      (node (ref "WPC") (pin "8") (pinfunction "8_8") (pintype "passive"))
    )
    (net (code "61") (name "LIN") (class "Default")
      (node (ref "R1") (pin "2") (pinfunction "2_2") (pintype "passive"))
      (node (ref "R5") (pin "2") (pinfunction "2_2") (pintype "passive"))
      (node (ref "U5") (pin "LOUT") (pinfunction "LOUT_LOUT") (pintype "bidirectional"))
      (node (ref "U5A") (pin "OUT2") (pinfunction "OUT2_OUT2") (pintype "bidirectional"))
    )
    (net (code "62") (name "LRCK") (class "Default")
      (node (ref "MPU1") (pin "P$35") (pinfunction "GPIO19_P$35") (pintype "bidirectional"))
      (node (ref "U5") (pin "LRCK") (pinfunction "LRCK_LRCK") (pintype "bidirectional"))
      (node (ref "U5A") (pin "MP10") (pinfunction "MP10_MP10") (pintype "bidirectional"))
      (node (ref "U5A") (pin "MP4") (pinfunction "MP4_MP4") (pintype "bidirectional"))
    )
    (net (code "63") (name "Net-(12V-DC-PadIN+)") (class "Default")
      (node (ref "12V-DC") (pin "IN+") (pinfunction "IN+_IN+") (pintype "bidirectional"))
      (node (ref "B1") (pin "+") (pinfunction "+_+") (pintype "passive"))
      (node (ref "C2") (pin "+") (pinfunction "+_+") (pintype "passive"))
      (node (ref "C3") (pin "+") (pinfunction "+_+") (pintype "passive"))
    )
    (net (code "64") (name "Net-(B1-AC1)") (class "Default")
      (node (ref "B1") (pin "AC2") (pinfunction "AC1_AC2") (pintype "passive"))
      (node (ref "F1") (pin "2A") (pinfunction "2_2A") (pintype "passive"))
    )
    (net (code "65") (name "Net-(B1-AC2)") (class "Default")
      (node (ref "B1") (pin "AC1") (pinfunction "AC2_AC1") (pintype "passive"))
      (node (ref "WPC-J501-AUX-PWR") (pin "1") (pinfunction "S_1") (pintype "passive"))
      (node (ref "WPC-J501-AUX-PWR") (pin "2") (pinfunction "S_2") (pintype "passive"))
    )
    (net (code "66") (name "Net-(BACKBOX-PadLIN)") (class "Default")
      (node (ref "BACKBOX") (pin "LIN") (pinfunction "LIN_LIN") (pintype "bidirectional"))
      (node (ref "R5") (pin "1") (pinfunction "1_1") (pintype "passive"))
    )
    (net (code "67") (name "Net-(BACKBOX-PadRIN)") (class "Default")
      (node (ref "BACKBOX") (pin "RIN") (pinfunction "RIN_RIN") (pintype "bidirectional"))
      (node (ref "R4") (pin "1") (pinfunction "1_1") (pintype "passive"))
    )
    (net (code "68") (name "Net-(DE-CN3-POTE-S)") (class "Default")
      (node (ref "DE-CN3-POT") (pin "5") (pinfunction "S_5") (pintype "passive"))
      (node (ref "U$1") (pin "PB0") (pinfunction "B0_PB0") (pintype "bidirectional"))
    )
    (net (code "69") (name "Net-(F1-1)") (class "Default")
      (node (ref "F1") (pin "1A") (pinfunction "1_1A") (pintype "passive"))
      (node (ref "WPC-J501-AUX-PWR") (pin "6") (pinfunction "S_6") (pintype "passive"))
      (node (ref "WPC-J501-AUX-PWR") (pin "7") (pinfunction "S_7") (pintype "passive"))
    )
    (net (code "70") (name "Net-(MPU1-ID_SC*)") (class "Default")
      (node (ref "MPU1") (pin "P$28") (pinfunction "ID_SC*_P$28") (pintype "bidirectional"))
      (node (ref "U$1") (pin "NRST") (pinfunction "R_NRST") (pintype "bidirectional"))
    )
    (net (code "71") (name "Net-(R3-Pad1)") (class "Default")
      (node (ref "R3") (pin "1") (pinfunction "1_1") (pintype "passive"))
      (node (ref "U5A") (pin "OUT3") (pinfunction "OUT3_OUT3") (pintype "bidirectional"))
    )
    (net (code "72") (name "Net-(RN3B-2)") (class "Default")
      (node (ref "RN3") (pin "4") (pinfunction "2_4") (pintype "passive"))
      (node (ref "U$1") (pin "PC14") (pinfunction "C14_PC14") (pintype "bidirectional"))
    )
    (net (code "73") (name "Net-(RN3C-2)") (class "Default")
      (node (ref "RN3") (pin "6") (pinfunction "2_6") (pintype "passive"))
      (node (ref "U$1") (pin "PA12") (pinfunction "A12_PA12") (pintype "bidirectional"))
    )
    (net (code "74") (name "Net-(RN3D-2)") (class "Default")
      (node (ref "RN3") (pin "8") (pinfunction "2_8") (pintype "passive"))
      (node (ref "U$1") (pin "PA11") (pinfunction "A11_PA11") (pintype "bidirectional"))
    )
    (net (code "75") (name "Net-(RN3E-2)") (class "Default")
      (node (ref "RN3") (pin "10") (pinfunction "2_10") (pintype "passive"))
      (node (ref "U$1") (pin "PA10") (pinfunction "A10_PA10") (pintype "bidirectional"))
    )
    (net (code "76") (name "Net-(RN4B-2)") (class "Default")
      (node (ref "RN4") (pin "4") (pinfunction "2_4") (pintype "passive"))
      (node (ref "U$1") (pin "PA4") (pinfunction "A4_PA4") (pintype "bidirectional"))
    )
    (net (code "77") (name "Net-(RN4C-2)") (class "Default")
      (node (ref "RN4") (pin "6") (pinfunction "2_6") (pintype "passive"))
      (node (ref "U$1") (pin "PA5") (pinfunction "A5_PA5") (pintype "bidirectional"))
    )
    (net (code "78") (name "Net-(RN4D-2)") (class "Default")
      (node (ref "RN4") (pin "8") (pinfunction "2_8") (pintype "passive"))
      (node (ref "U$1") (pin "PA6") (pinfunction "A6_PA6") (pintype "bidirectional"))
    )
    (net (code "79") (name "Net-(RN4E-2)") (class "Default")
      (node (ref "RN4") (pin "10") (pinfunction "2_10") (pintype "passive"))
      (node (ref "U$1") (pin "PA7") (pinfunction "A7_PA7") (pintype "bidirectional"))
    )
    (net (code "80") (name "Net-(RN5B-2)") (class "Default")
      (node (ref "RN5") (pin "4") (pinfunction "2_4") (pintype "passive"))
      (node (ref "U$1") (pin "PA8") (pinfunction "A8_PA8") (pintype "bidirectional"))
    )
    (net (code "81") (name "Net-(RN5C-2)") (class "Default")
      (node (ref "R6") (pin "1") (pinfunction "1_1") (pintype "passive"))
      (node (ref "RN5") (pin "6") (pinfunction "2_6") (pintype "passive"))
    )
    (net (code "82") (name "Net-(RN5D-2)") (class "Default")
      (node (ref "RN5") (pin "8") (pinfunction "2_8") (pintype "passive"))
      (node (ref "U$1") (pin "PA1") (pinfunction "A1_PA1") (pintype "bidirectional"))
    )
    (net (code "83") (name "Net-(RN5E-2)") (class "Default")
      (node (ref "RN5") (pin "10") (pinfunction "2_10") (pintype "passive"))
      (node (ref "U$1") (pin "PA2") (pinfunction "A2_PA2") (pintype "bidirectional"))
    )
    (net (code "84") (name "Net-(U$1-A0)") (class "Default")
      (node (ref "R6") (pin "2") (pinfunction "2_2") (pintype "passive"))
      (node (ref "U$1") (pin "PA0") (pinfunction "A0_PA0") (pintype "bidirectional"))
    )
    (net (code "85") (name "Net-(U$1-A3)") (class "Default")
      (node (ref "RN4") (pin "2") (pinfunction "2_2") (pintype "passive"))
      (node (ref "U$1") (pin "PA3") (pinfunction "A3_PA3") (pintype "bidirectional"))
    )
    (net (code "86") (name "Net-(U$1-A9)") (class "Default")
      (node (ref "RN5") (pin "2") (pinfunction "2_2") (pintype "passive"))
      (node (ref "U$1") (pin "PA9") (pinfunction "A9_PA9") (pintype "bidirectional"))
    )
    (net (code "87") (name "Net-(U$1-C15)") (class "Default")
      (node (ref "RN3") (pin "2") (pinfunction "2_2") (pintype "passive"))
      (node (ref "U$1") (pin "PC15") (pinfunction "C15_PC15") (pintype "bidirectional"))
    )
    (net (code "88") (name "Net-(U5-PadA3V3)") (class "Default")
      (node (ref "U5") (pin "A3V3") (pinfunction "A3V3_A3V3") (pintype "bidirectional"))
      (node (ref "U5") (pin "XSMT") (pinfunction "XSMT_XSMT") (pintype "bidirectional"))
    )
    (net (code "89") (name "RIN") (class "Default")
      (node (ref "R2") (pin "2") (pinfunction "2_2") (pintype "passive"))
      (node (ref "R4") (pin "2") (pinfunction "2_2") (pintype "passive"))
      (node (ref "U5") (pin "ROUT") (pinfunction "ROUT_ROUT") (pintype "bidirectional"))
      (node (ref "U5A") (pin "OUT1") (pinfunction "OUT1_OUT1") (pintype "bidirectional"))
    )
    (net (code "90") (name "SCL") (class "Default")
      (node (ref "DISPLAY") (pin "3") (pinfunction "SCL_3") (pintype "bidirectional"))
      (node (ref "DISPLAY") (pin "7") (pinfunction "SCL_7") (pintype "bidirectional"))
      (node (ref "I2C_3V3") (pin "2") (pinfunction "2_2") (pintype "passive"))
      (node (ref "MPU1") (pin "P$5") (pinfunction "GPIO3_P$5") (pintype "bidirectional"))
      (node (ref "U$1") (pin "PB6") (pinfunction "B6_PB6") (pintype "bidirectional"))
      (node (ref "U5A") (pin "SCL") (pinfunction "SCL_SCL") (pintype "bidirectional"))
    )
    (net (code "91") (name "SDA") (class "Default")
      (node (ref "DISPLAY") (pin "4") (pinfunction "SDA_4") (pintype "bidirectional"))
      (node (ref "DISPLAY") (pin "8") (pinfunction "SDA_8") (pintype "bidirectional"))
      (node (ref "I2C_3V3") (pin "1") (pinfunction "1_1") (pintype "passive"))
      (node (ref "MPU1") (pin "P$3") (pinfunction "GPIO2_P$3") (pintype "bidirectional"))
      (node (ref "U$1") (pin "PB7") (pinfunction "B7_PB7") (pintype "bidirectional"))
      (node (ref "U5A") (pin "SDA") (pinfunction "SDA_SDA") (pintype "bidirectional"))
    )
    (net (code "92") (name "unconnected-(BACKBOX-PadNC1)") (class "Default")
      (node (ref "BACKBOX") (pin "NC1") (pinfunction "NC1_NC1") (pintype "bidirectional"))
    )
    (net (code "93") (name "unconnected-(BACKBOX-PadNC2)") (class "Default")
      (node (ref "BACKBOX") (pin "NC2") (pinfunction "NC2_NC2") (pintype "bidirectional"))
    )
    (net (code "94") (name "unconnected-(BB-AMP-PadSWA)") (class "Default")
      (node (ref "BB-AMP") (pin "SWA") (pinfunction "SWA_SWA") (pintype "input"))
    )
    (net (code "95") (name "unconnected-(BB-AMP-PadSWB)") (class "Default")
      (node (ref "BB-AMP") (pin "SWB") (pinfunction "SWB_SWB") (pintype "bidirectional"))
    )
    (net (code "96") (name "unconnected-(CAB-AMP-PadOUT.R+)") (class "Default")
      (node (ref "CAB-AMP") (pin "OUT.R+") (pinfunction "OUT.R+_OUT.R+") (pintype "output"))
    )
    (net (code "97") (name "unconnected-(CAB-AMP-PadOUT.R-)") (class "Default")
      (node (ref "CAB-AMP") (pin "OUT.R-") (pinfunction "OUT.R-_OUT.R-") (pintype "output"))
    )
    (net (code "98") (name "unconnected-(CAB-AMP-PadSWA)") (class "Default")
      (node (ref "CAB-AMP") (pin "SWA") (pinfunction "SWA_SWA") (pintype "input"))
    )
    (net (code "99") (name "unconnected-(CAB-AMP-PadSWB)") (class "Default")
      (node (ref "CAB-AMP") (pin "SWB") (pinfunction "SWB_SWB") (pintype "bidirectional"))
    )
    (net (code "100") (name "unconnected-(CABINET-PadNC1)") (class "Default")
      (node (ref "CABINET") (pin "NC1") (pinfunction "NC1_NC1") (pintype "bidirectional"))
    )
    (net (code "101") (name "unconnected-(CABINET-PadNC2)") (class "Default")
      (node (ref "CABINET") (pin "NC2") (pinfunction "NC2_NC2") (pintype "bidirectional"))
    )
    (net (code "102") (name "unconnected-(CABINET-PadRIN)") (class "Default")
      (node (ref "CABINET") (pin "RIN") (pinfunction "RIN_RIN") (pintype "bidirectional"))
    )
    (net (code "103") (name "unconnected-(CABINET-PadROUT)") (class "Default")
      (node (ref "CABINET") (pin "ROUT") (pinfunction "ROUT_ROUT") (pintype "bidirectional"))
    )
    (net (code "104") (name "unconnected-(DATAEAST-Pad2)") (class "Default")
      (node (ref "DATAEAST") (pin "2") (pinfunction "2_2") (pintype "passive"))
    )
    (net (code "105") (name "unconnected-(DATAEAST-Pad11)") (class "Default")
      (node (ref "DATAEAST") (pin "11") (pinfunction "11_11") (pintype "passive"))
    )
    (net (code "106") (name "unconnected-(DATAEAST-Pad14)") (class "Default")
      (node (ref "DATAEAST") (pin "14") (pinfunction "14_14") (pintype "passive"))
    )
    (net (code "107") (name "unconnected-(DATAEAST-Pad15)") (class "Default")
      (node (ref "DATAEAST") (pin "15") (pinfunction "15_15") (pintype "passive"))
    )
    (net (code "108") (name "unconnected-(DATAEAST-Pad17)") (class "Default")
      (node (ref "DATAEAST") (pin "17") (pinfunction "17_17") (pintype "passive"))
    )
    (net (code "109") (name "unconnected-(DATAEAST-Pad18)") (class "Default")
      (node (ref "DATAEAST") (pin "18") (pinfunction "18_18") (pintype "passive"))
    )
    (net (code "110") (name "unconnected-(DATAEAST-Pad19)") (class "Default")
      (node (ref "DATAEAST") (pin "19") (pinfunction "19_19") (pintype "passive"))
    )
    (net (code "111") (name "unconnected-(DATAEAST-Pad20)") (class "Default")
      (node (ref "DATAEAST") (pin "20") (pinfunction "20_20") (pintype "passive"))
    )
    (net (code "112") (name "unconnected-(DE-CN2-POWERB-S-Pad2)") (class "Default")
      (node (ref "DE-CN2-POWER") (pin "2") (pinfunction "S_2") (pintype "passive"))
    )
    (net (code "113") (name "unconnected-(DE-CN2-POWERC-S-Pad3)") (class "Default")
      (node (ref "DE-CN2-POWER") (pin "3") (pinfunction "S_3") (pintype "passive"))
    )
    (net (code "114") (name "unconnected-(DE-CN2-POWERD-S-Pad4)") (class "Default")
      (node (ref "DE-CN2-POWER") (pin "4") (pinfunction "S_4") (pintype "passive"))
    )
    (net (code "115") (name "unconnected-(DE-CN2-POWERF-S-Pad6)") (class "Default")
      (node (ref "DE-CN2-POWER") (pin "6") (pinfunction "S_6") (pintype "passive"))
    )
    (net (code "116") (name "unconnected-(DE-CN3-POTA-S-Pad1)") (class "Default")
      (node (ref "DE-CN3-POT") (pin "1") (pinfunction "S_1") (pintype "passive"))
    )
    (net (code "117") (name "unconnected-(DE-CN3-POTB-S-Pad2)") (class "Default")
      (node (ref "DE-CN3-POT") (pin "2") (pinfunction "S_2") (pintype "passive"))
    )
    (net (code "118") (name "unconnected-(DE-CN3-POTC-S-Pad3)") (class "Default")
      (node (ref "DE-CN3-POT") (pin "3") (pinfunction "S_3") (pintype "passive"))
    )
    (net (code "119") (name "unconnected-(DE-CN4-SPEAKERC-S-Pad3)") (class "Default")
      (node (ref "DE-CN4-SPEAKER") (pin "3") (pinfunction "S_3") (pintype "passive"))
    )
    (net (code "120") (name "unconnected-(J1-PadRSH)") (class "Default")
      (node (ref "J1") (pin "RSH") (pinfunction "RSH_RSH") (pintype "bidirectional"))
    )
    (net (code "121") (name "unconnected-(J1-PadTSH)") (class "Default")
      (node (ref "J1") (pin "TSH") (pinfunction "TSH_TSH") (pintype "bidirectional"))
    )
    (net (code "122") (name "unconnected-(MPU1-3V3-PadP$17)") (class "Default")
      (node (ref "MPU1") (pin "P$17") (pinfunction "3V3_P$17") (pintype "bidirectional"))
    )
    (net (code "123") (name "unconnected-(MPU1-GPIO8-PadP$24)") (class "Default")
      (node (ref "MPU1") (pin "P$24") (pinfunction "GPIO8_P$24") (pintype "bidirectional"))
    )
    (net (code "124") (name "unconnected-(MPU1-GPIO12-PadP$32)") (class "Default")
      (node (ref "MPU1") (pin "P$32") (pinfunction "GPIO12_P$32") (pintype "bidirectional"))
    )
    (net (code "125") (name "unconnected-(MPU1-GPIO20-PadP$38)") (class "Default")
      (node (ref "MPU1") (pin "P$38") (pinfunction "GPIO20_P$38") (pintype "bidirectional"))
    )
    (net (code "126") (name "unconnected-(MPU1-ID_SD*-PadP$27)") (class "Default")
      (node (ref "MPU1") (pin "P$27") (pinfunction "ID_SD*_P$27") (pintype "bidirectional"))
    )
    (net (code "127") (name "unconnected-(PIN2DMDA-S-Pad1)") (class "Default")
      (node (ref "PIN2DMD") (pin "1") (pinfunction "S_1") (pintype "passive"))
    )
    (net (code "128") (name "unconnected-(PIN2DMDD-S-Pad4)") (class "Default")
      (node (ref "PIN2DMD") (pin "4") (pinfunction "S_4") (pintype "passive"))
    )
    (net (code "129") (name "unconnected-(U$1-5V-PadP5V)") (class "Default")
      (node (ref "U$1") (pin "P5V") (pinfunction "5V_P5V") (pintype "bidirectional"))
    )
    (net (code "130") (name "unconnected-(U$1-B1-PadPB1)") (class "Default")
      (node (ref "U$1") (pin "PB1") (pinfunction "B1_PB1") (pintype "bidirectional"))
    )
    (net (code "131") (name "unconnected-(U$1-B8-PadPB8)") (class "Default")
      (node (ref "U$1") (pin "PB8") (pinfunction "B8_PB8") (pintype "bidirectional"))
    )
    (net (code "132") (name "unconnected-(U$1-B10-PadPB10)") (class "Default")
      (node (ref "U$1") (pin "PB10") (pinfunction "B10_PB10") (pintype "bidirectional"))
    )
    (net (code "133") (name "unconnected-(U$1-C13-PadPC13)") (class "Default")
      (node (ref "U$1") (pin "PC13") (pinfunction "C13_PC13") (pintype "bidirectional"))
    )
    (net (code "134") (name "unconnected-(U$1-P3.3_2-PadP3V3_2)") (class "Default")
      (node (ref "U$1") (pin "P3V3_2") (pinfunction "P3.3_2_P3V3_2") (pintype "bidirectional"))
    )
    (net (code "135") (name "unconnected-(U$1-PadP3V3_3)") (class "Default")
      (node (ref "U$1") (pin "P3V3_3") (pinfunction "P3V3_3_P3V3_3") (pintype "bidirectional"))
    )
    (net (code "136") (name "unconnected-(U$1-PadVB)") (class "Default")
      (node (ref "U$1") (pin "VB") (pinfunction "VB_VB") (pintype "bidirectional"))
    )
    (net (code "137") (name "unconnected-(U$2-PadCTRL)") (class "Default")
      (node (ref "U$2") (pin "CTRL") (pinfunction "CTRL_CTRL") (pintype "bidirectional"))
    )
    (net (code "138") (name "unconnected-(U$3-PadCTRL)") (class "Default")
      (node (ref "U$3") (pin "CTRL") (pinfunction "CTRL_CTRL") (pintype "bidirectional"))
    )
    (net (code "139") (name "unconnected-(U$3-PadROUT+)") (class "Default")
      (node (ref "U$3") (pin "ROUT+") (pinfunction "ROUT+_ROUT+") (pintype "bidirectional"))
    )
    (net (code "140") (name "unconnected-(U$3-PadROUT-)") (class "Default")
      (node (ref "U$3") (pin "ROUT-") (pinfunction "ROUT-_ROUT-") (pintype "bidirectional"))
    )
    (net (code "141") (name "unconnected-(U5A-PadCLKI)") (class "Default")
      (node (ref "U5A") (pin "CLKI") (pinfunction "CLKI_CLKI") (pintype "bidirectional"))
    )
    (net (code "142") (name "unconnected-(U5A-PadCLKO)") (class "Default")
      (node (ref "U5A") (pin "CLKO") (pinfunction "CLKO_CLKO") (pintype "bidirectional"))
    )
    (net (code "143") (name "unconnected-(U5A-PadMP1)") (class "Default")
      (node (ref "U5A") (pin "MP1") (pinfunction "MP1_MP1") (pintype "bidirectional"))
    )
    (net (code "144") (name "unconnected-(U5A-PadMP2)") (class "Default")
      (node (ref "U5A") (pin "MP2") (pinfunction "MP2_MP2") (pintype "bidirectional"))
    )
    (net (code "145") (name "unconnected-(U5A-PadMP3)") (class "Default")
      (node (ref "U5A") (pin "MP3") (pinfunction "MP3_MP3") (pintype "bidirectional"))
    )
    (net (code "146") (name "unconnected-(U5A-PadMP6)") (class "Default")
      (node (ref "U5A") (pin "MP6") (pinfunction "MP6_MP6") (pintype "bidirectional"))
    )
    (net (code "147") (name "unconnected-(U5A-PadMP7)") (class "Default")
      (node (ref "U5A") (pin "MP7") (pinfunction "MP7_MP7") (pintype "bidirectional"))
    )
    (net (code "148") (name "unconnected-(U5A-PadMP8)") (class "Default")
      (node (ref "U5A") (pin "MP8") (pinfunction "MP8_MP8") (pintype "bidirectional"))
    )
    (net (code "149") (name "unconnected-(U5A-PadMP9)") (class "Default")
      (node (ref "U5A") (pin "MP9") (pinfunction "MP9_MP9") (pintype "bidirectional"))
    )
    (net (code "150") (name "unconnected-(U5A-PadOUT4)") (class "Default")
      (node (ref "U5A") (pin "OUT4") (pinfunction "OUT4_OUT4") (pintype "bidirectional"))
    )
    (net (code "151") (name "unconnected-(U5A-PadWP)") (class "Default")
      (node (ref "U5A") (pin "WP") (pinfunction "WP_WP") (pintype "bidirectional"))
    )
    (net (code "152") (name "unconnected-(WPC-J501-AUX-PWRC-S-Pad3)") (class "Default")
      (node (ref "WPC-J501-AUX-PWR") (pin "3") (pinfunction "S_3") (pintype "passive"))
    )
    (net (code "153") (name "unconnected-(WPC-J501-AUX-PWRD-S-Pad4)") (class "Default")
      (node (ref "WPC-J501-AUX-PWR") (pin "4") (pinfunction "S_4") (pintype "passive"))
    )
    (net (code "154") (name "unconnected-(WPC-J501-AUX-PWRE-S-Pad5)") (class "Default")
      (node (ref "WPC-J501-AUX-PWR") (pin "5") (pinfunction "S_5") (pintype "passive"))
    )
    (net (code "155") (name "unconnected-(WPC-J504-CAB-SPKB-S-Pad2)") (class "Default")
      (node (ref "WPC-J504-CAB-SPK") (pin "2") (pinfunction "S_2") (pintype "passive"))
    )
    (net (code "156") (name "unconnected-(WPC-J504-CAB-SPKC-S-Pad3)") (class "Default")
      (node (ref "WPC-J504-CAB-SPK") (pin "3") (pinfunction "S_3") (pintype "passive"))
    )
    (net (code "157") (name "unconnected-(WPC-Pad27)") (class "Default")
      (node (ref "WPC") (pin "27") (pinfunction "27_27") (pintype "passive"))
    )
    (net (code "158") (name "unconnected-(WPC-Pad32)") (class "Default")
      (node (ref "WPC") (pin "32") (pinfunction "32_32") (pintype "passive"))
    )
    (net (code "159") (name "unconnected-(WPC-Pad33)") (class "Default")
      (node (ref "WPC") (pin "33") (pinfunction "33_33") (pintype "passive"))
    )
    (net (code "160") (name "unconnected-(WPC-Pad34)") (class "Default")
      (node (ref "WPC") (pin "34") (pinfunction "34_34") (pintype "passive"))
    )
  )
)
